# G803A.net
KiCad netlist of a schematic drawn in EAGLE
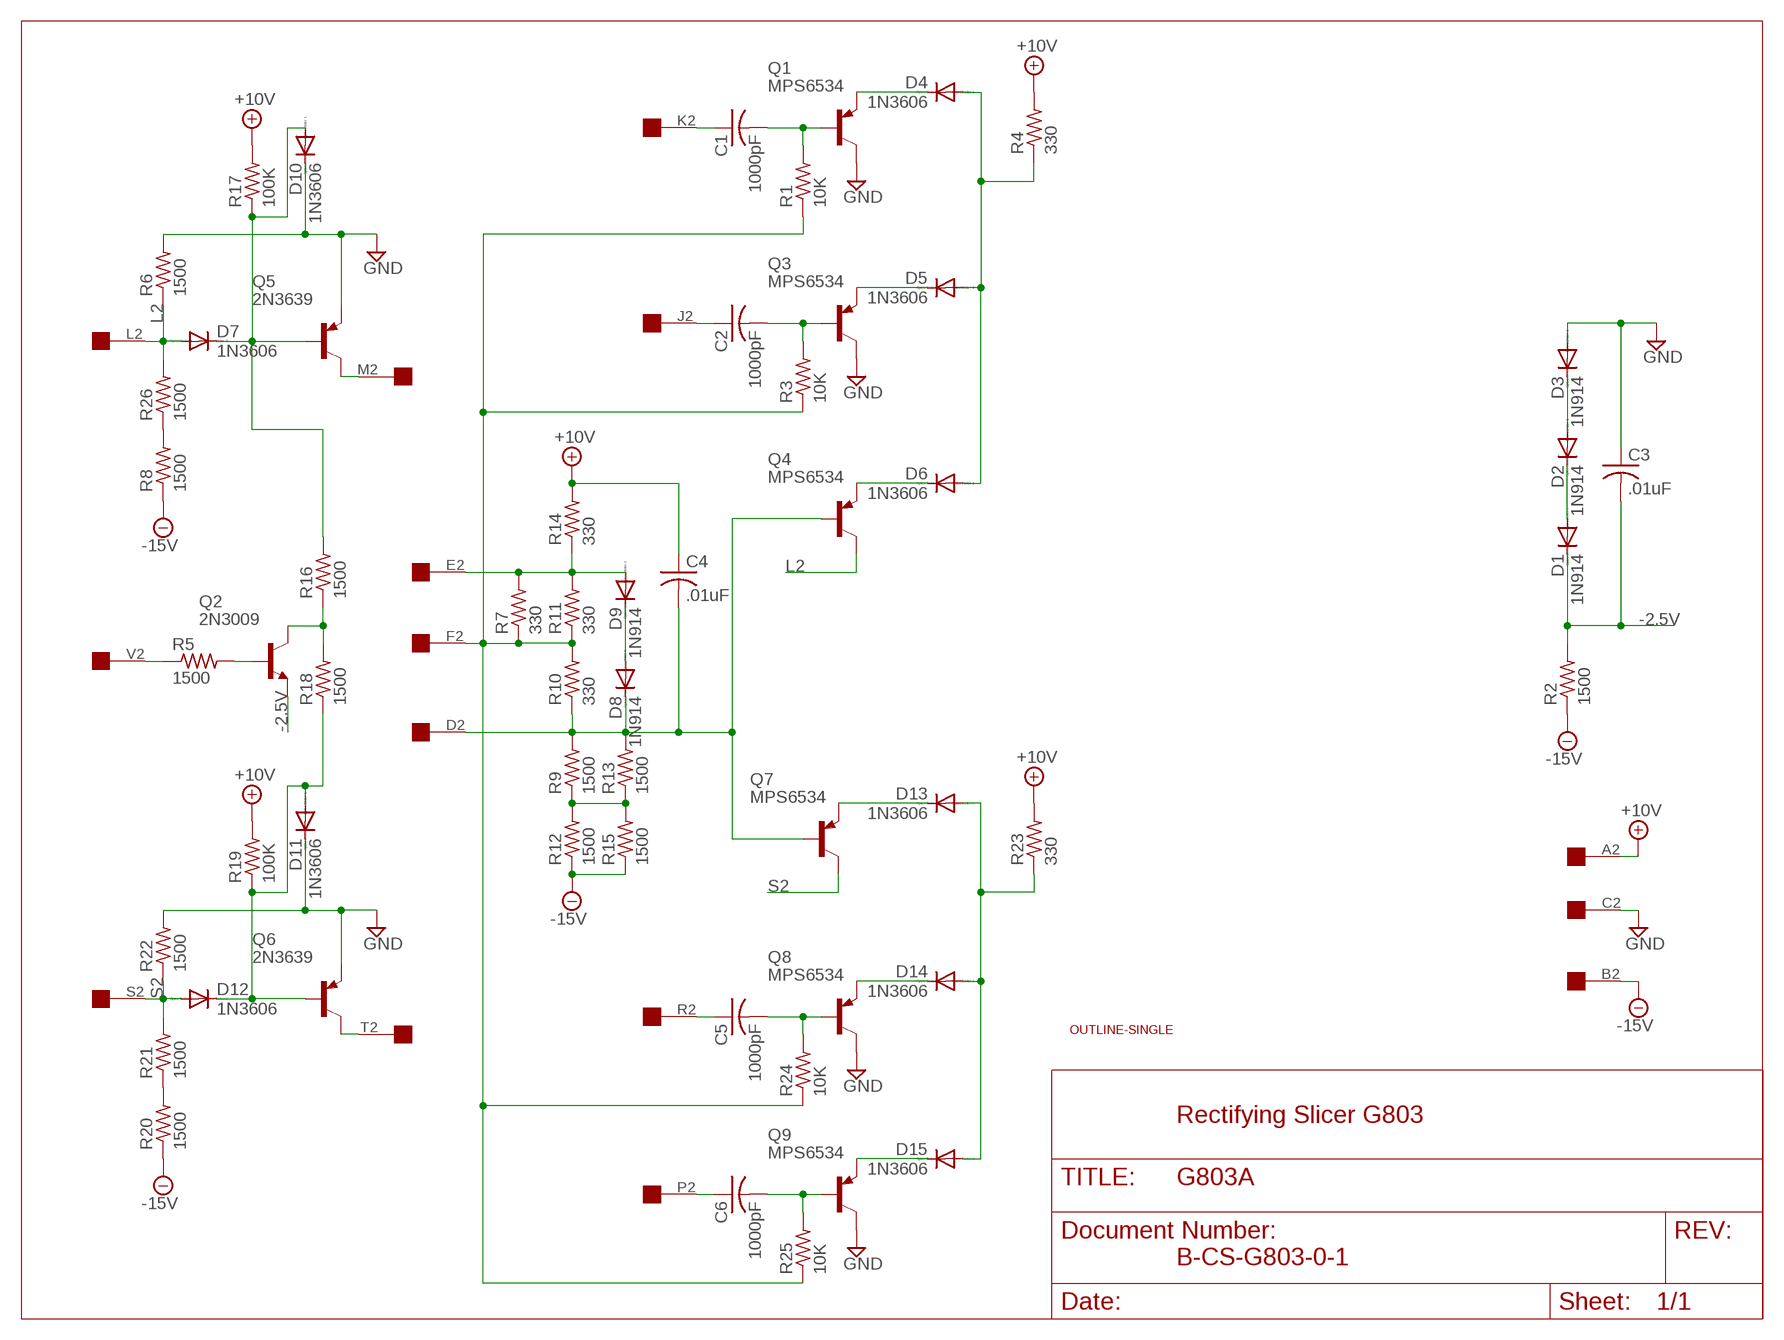
[diagram p0: schematic, sheet 1]

(export (version "E")
  (design (tool "Eeschema 10.0.6"))
  (components
    (comp (ref "C1")
      (value "1000pF")
      (footprint "eagle-import:C075-032X103")
      (libsource (lib "eagle-import") (part "C-US075-032X103"))
    )
    (comp (ref "C2")
      (value "1000pF")
      (footprint "eagle-import:C075-032X103")
      (libsource (lib "eagle-import") (part "C-US075-032X103"))
    )
    (comp (ref "C3")
      (value ".01uF")
      (footprint "eagle-import:C050-025X075")
      (libsource (lib "eagle-import") (part "C-US050-025X075"))
    )
    (comp (ref "C4")
      (value ".01uF")
      (footprint "eagle-import:C075-032X103")
      (libsource (lib "eagle-import") (part "C-US075-032X103"))
    )
    (comp (ref "C5")
      (value "1000pF")
      (footprint "eagle-import:C075-032X103")
      (libsource (lib "eagle-import") (part "C-US075-032X103"))
    )
    (comp (ref "C6")
      (value "1000pF")
      (footprint "eagle-import:C075-032X103")
      (libsource (lib "eagle-import") (part "C-US075-032X103"))
    )
    (comp (ref "D1")
      (value "1N914")
      (footprint "eagle-import:DO35-10")
      (libsource (lib "eagle-import") (part "1N4148DO35-10"))
    )
    (comp (ref "D2")
      (value "1N914")
      (footprint "eagle-import:DO35-10")
      (libsource (lib "eagle-import") (part "1N4148DO35-10"))
    )
    (comp (ref "D3")
      (value "1N914")
      (footprint "eagle-import:DO35-10")
      (libsource (lib "eagle-import") (part "1N4148DO35-10"))
    )
    (comp (ref "D4")
      (value "1N3606")
      (footprint "eagle-import:DO35-10")
      (libsource (lib "eagle-import") (part "1N4148DO35-10"))
    )
    (comp (ref "D5")
      (value "1N3606")
      (footprint "eagle-import:DO35-10")
      (libsource (lib "eagle-import") (part "1N4148DO35-10"))
    )
    (comp (ref "D6")
      (value "1N3606")
      (footprint "eagle-import:DO35-10")
      (libsource (lib "eagle-import") (part "1N4148DO35-10"))
    )
    (comp (ref "D7")
      (value "1N3606")
      (footprint "eagle-import:DO35-10")
      (libsource (lib "eagle-import") (part "1N4148DO35-10"))
    )
    (comp (ref "D8")
      (value "1N914")
      (footprint "eagle-import:DO35-10")
      (libsource (lib "eagle-import") (part "1N4148DO35-10"))
    )
    (comp (ref "D9")
      (value "1N914")
      (footprint "eagle-import:DO35-10")
      (libsource (lib "eagle-import") (part "1N4148DO35-10"))
    )
    (comp (ref "D10")
      (value "1N3606")
      (footprint "eagle-import:DO35-10")
      (libsource (lib "eagle-import") (part "1N4148DO35-10"))
    )
    (comp (ref "D11")
      (value "1N3606")
      (footprint "eagle-import:DO35-10")
      (libsource (lib "eagle-import") (part "1N4148DO35-10"))
    )
    (comp (ref "D12")
      (value "1N3606")
      (footprint "eagle-import:DO35-10")
      (libsource (lib "eagle-import") (part "1N4148DO35-10"))
    )
    (comp (ref "D13")
      (value "1N3606")
      (footprint "eagle-import:DO35-10")
      (libsource (lib "eagle-import") (part "1N4148DO35-10"))
    )
    (comp (ref "D14")
      (value "1N3606")
      (footprint "eagle-import:DO35-10")
      (libsource (lib "eagle-import") (part "1N4148DO35-10"))
    )
    (comp (ref "D15")
      (value "1N3606")
      (footprint "eagle-import:DO35-10")
      (libsource (lib "eagle-import") (part "1N4148DO35-10"))
    )
    (comp (ref "Q1")
      (value "MPS6534")
      (footprint "eagle-import:TO39")
      (libsource (lib "eagle-import") (part "2N2904"))
    )
    (comp (ref "Q2")
      (value "2N3009")
      (footprint "eagle-import:TO5")
      (libsource (lib "eagle-import") (part "2N2102"))
    )
    (comp (ref "Q3")
      (value "MPS6534")
      (footprint "eagle-import:TO39")
      (libsource (lib "eagle-import") (part "2N2904"))
    )
    (comp (ref "Q4")
      (value "MPS6534")
      (footprint "eagle-import:TO39")
      (libsource (lib "eagle-import") (part "2N2904"))
    )
    (comp (ref "Q5")
      (value "2N3639")
      (footprint "eagle-import:TO39")
      (libsource (lib "eagle-import") (part "2N2904"))
    )
    (comp (ref "Q6")
      (value "2N3639")
      (footprint "eagle-import:TO39")
      (libsource (lib "eagle-import") (part "2N2904"))
    )
    (comp (ref "Q7")
      (value "MPS6534")
      (footprint "eagle-import:TO39")
      (libsource (lib "eagle-import") (part "2N2904"))
    )
    (comp (ref "Q8")
      (value "MPS6534")
      (footprint "eagle-import:TO39")
      (libsource (lib "eagle-import") (part "2N2904"))
    )
    (comp (ref "Q9")
      (value "MPS6534")
      (footprint "eagle-import:TO39")
      (libsource (lib "eagle-import") (part "2N2904"))
    )
    (comp (ref "R1")
      (value "10K")
      (footprint "eagle-import:0207_10")
      (libsource (lib "eagle-import") (part "R-US_0207/10"))
    )
    (comp (ref "R2")
      (value "1500")
      (footprint "eagle-import:0207_10")
      (libsource (lib "eagle-import") (part "R-US_0207/10"))
    )
    (comp (ref "R3")
      (value "10K")
      (footprint "eagle-import:0207_10")
      (libsource (lib "eagle-import") (part "R-US_0207/10"))
    )
    (comp (ref "R4")
      (value "330")
      (footprint "eagle-import:0207_10")
      (libsource (lib "eagle-import") (part "R-US_0207/10"))
    )
    (comp (ref "R5")
      (value "1500")
      (footprint "eagle-import:0207_10")
      (libsource (lib "eagle-import") (part "R-US_0207/10"))
    )
    (comp (ref "R6")
      (value "1500")
      (footprint "eagle-import:0207_10")
      (libsource (lib "eagle-import") (part "R-US_0207/10"))
    )
    (comp (ref "R7")
      (value "330")
      (footprint "eagle-import:0207_10")
      (libsource (lib "eagle-import") (part "R-US_0207/10"))
    )
    (comp (ref "R8")
      (value "1500")
      (footprint "eagle-import:0207_10")
      (libsource (lib "eagle-import") (part "R-US_0207/10"))
    )
    (comp (ref "R9")
      (value "1500")
      (footprint "eagle-import:0207_10")
      (libsource (lib "eagle-import") (part "R-US_0207/10"))
    )
    (comp (ref "R10")
      (value "330")
      (footprint "eagle-import:0207_10")
      (libsource (lib "eagle-import") (part "R-US_0207/10"))
    )
    (comp (ref "R11")
      (value "330")
      (footprint "eagle-import:0207_10")
      (libsource (lib "eagle-import") (part "R-US_0207/10"))
    )
    (comp (ref "R12")
      (value "1500")
      (footprint "eagle-import:0207_10")
      (libsource (lib "eagle-import") (part "R-US_0207/10"))
    )
    (comp (ref "R13")
      (value "1500")
      (footprint "eagle-import:0207_10")
      (libsource (lib "eagle-import") (part "R-US_0207/10"))
    )
    (comp (ref "R14")
      (value "330")
      (footprint "eagle-import:0207_10")
      (libsource (lib "eagle-import") (part "R-US_0207/10"))
    )
    (comp (ref "R15")
      (value "1500")
      (footprint "eagle-import:0207_10")
      (libsource (lib "eagle-import") (part "R-US_0207/10"))
    )
    (comp (ref "R16")
      (value "1500")
      (footprint "eagle-import:0207_10")
      (libsource (lib "eagle-import") (part "R-US_0207/10"))
    )
    (comp (ref "R17")
      (value "100K")
      (footprint "eagle-import:0207_10")
      (libsource (lib "eagle-import") (part "R-US_0207/10"))
    )
    (comp (ref "R18")
      (value "1500")
      (footprint "eagle-import:0207_10")
      (libsource (lib "eagle-import") (part "R-US_0207/10"))
    )
    (comp (ref "R19")
      (value "100K")
      (footprint "eagle-import:0207_10")
      (libsource (lib "eagle-import") (part "R-US_0207/10"))
    )
    (comp (ref "R20")
      (value "1500")
      (footprint "eagle-import:0207_10")
      (libsource (lib "eagle-import") (part "R-US_0207/10"))
    )
    (comp (ref "R21")
      (value "1500")
      (footprint "eagle-import:0207_10")
      (libsource (lib "eagle-import") (part "R-US_0207/10"))
    )
    (comp (ref "R22")
      (value "1500")
      (footprint "eagle-import:0207_10")
      (libsource (lib "eagle-import") (part "R-US_0207/10"))
    )
    (comp (ref "R23")
      (value "330")
      (footprint "eagle-import:0207_10")
      (libsource (lib "eagle-import") (part "R-US_0207/10"))
    )
    (comp (ref "R24")
      (value "10K")
      (footprint "eagle-import:0207_10")
      (libsource (lib "eagle-import") (part "R-US_0207/10"))
    )
    (comp (ref "R25")
      (value "10K")
      (footprint "eagle-import:0207_10")
      (libsource (lib "eagle-import") (part "R-US_0207/10"))
    )
    (comp (ref "R26")
      (value "1500")
      (footprint "eagle-import:0207_10")
      (libsource (lib "eagle-import") (part "R-US_0207/10"))
    )
    (comp (ref "U$1")
      (value "OUTLINE-SINGLE")
      (footprint "eagle-import:SINGLE")
      (libsource (lib "eagle-import") (part "OUTLINE-SINGLE"))
    )
    (comp (ref "U$2")
      (value "EDGE-1")
      (footprint "eagle-import:EDGE-CON1")
      (libsource (lib "eagle-import") (part "EDGE-1"))
    )
  )
  (nets
    (net (code "1") (name "+10V") (class "Default")
      (node (ref "C4") (pin "1") (pinfunction "1_1") (pintype "passive"))
      (node (ref "R14") (pin "2") (pinfunction "2_2") (pintype "passive"))
      (node (ref "R17") (pin "2") (pinfunction "2_2") (pintype "passive"))
      (node (ref "R19") (pin "2") (pinfunction "2_2") (pintype "passive"))
      (node (ref "R23") (pin "2") (pinfunction "2_2") (pintype "passive"))
      (node (ref "R4") (pin "2") (pinfunction "2_2") (pintype "passive"))
      (node (ref "U$2") (pin "A2") (pinfunction "1_A2") (pintype "bidirectional"))
    )
    (net (code "2") (name "-15V") (class "Default")
      (node (ref "R12") (pin "1") (pinfunction "1_1") (pintype "passive"))
      (node (ref "R15") (pin "1") (pinfunction "1_1") (pintype "passive"))
      (node (ref "R2") (pin "1") (pinfunction "1_1") (pintype "passive"))
      (node (ref "R20") (pin "1") (pinfunction "1_1") (pintype "passive"))
      (node (ref "R8") (pin "1") (pinfunction "1_1") (pintype "passive"))
      (node (ref "U$2") (pin "B2") (pinfunction "1_B2") (pintype "bidirectional"))
    )
    (net (code "3") (name "/-2.5V") (class "Default")
      (node (ref "C3") (pin "2") (pinfunction "2_2") (pintype "passive"))
      (node (ref "D1") (pin "C") (pinfunction "C_C") (pintype "passive"))
      (node (ref "Q2") (pin "1") (pinfunction "E_1") (pintype "passive"))
      (node (ref "R2") (pin "2") (pinfunction "2_2") (pintype "passive"))
    )
    (net (code "4") (name "/L2") (class "Default")
      (node (ref "D7") (pin "A") (pinfunction "A_A") (pintype "passive"))
      (node (ref "Q4") (pin "3") (pinfunction "C_3") (pintype "passive"))
      (node (ref "R26") (pin "2") (pinfunction "2_2") (pintype "passive"))
      (node (ref "R6") (pin "1") (pinfunction "1_1") (pintype "passive"))
      (node (ref "U$2") (pin "L2") (pinfunction "1_L2") (pintype "bidirectional"))
    )
    (net (code "5") (name "/S2") (class "Default")
      (node (ref "D12") (pin "A") (pinfunction "A_A") (pintype "passive"))
      (node (ref "Q7") (pin "3") (pinfunction "C_3") (pintype "passive"))
      (node (ref "R21") (pin "2") (pinfunction "2_2") (pintype "passive"))
      (node (ref "R22") (pin "1") (pinfunction "1_1") (pintype "passive"))
      (node (ref "U$2") (pin "S2") (pinfunction "1_S2") (pintype "bidirectional"))
    )
    (net (code "6") (name "GND") (class "Default")
      (node (ref "C3") (pin "1") (pinfunction "1_1") (pintype "passive"))
      (node (ref "D10") (pin "C") (pinfunction "C_C") (pintype "passive"))
      (node (ref "D11") (pin "C") (pinfunction "C_C") (pintype "passive"))
      (node (ref "D3") (pin "A") (pinfunction "A_A") (pintype "passive"))
      (node (ref "Q1") (pin "3") (pinfunction "C_3") (pintype "passive"))
      (node (ref "Q3") (pin "3") (pinfunction "C_3") (pintype "passive"))
      (node (ref "Q5") (pin "1") (pinfunction "E_1") (pintype "passive"))
      (node (ref "Q6") (pin "1") (pinfunction "E_1") (pintype "passive"))
      (node (ref "Q8") (pin "3") (pinfunction "C_3") (pintype "passive"))
      (node (ref "Q9") (pin "3") (pinfunction "C_3") (pintype "passive"))
      (node (ref "R22") (pin "2") (pinfunction "2_2") (pintype "passive"))
      (node (ref "R6") (pin "2") (pinfunction "2_2") (pintype "passive"))
      (node (ref "U$2") (pin "C2") (pinfunction "1_C2") (pintype "bidirectional"))
    )
    (net (code "7") (name "Net-(D1-PadA)") (class "Default")
      (node (ref "D1") (pin "A") (pinfunction "A_A") (pintype "passive"))
      (node (ref "D2") (pin "C") (pinfunction "C_C") (pintype "passive"))
    )
    (net (code "8") (name "Net-(D2-PadA)") (class "Default")
      (node (ref "D2") (pin "A") (pinfunction "A_A") (pintype "passive"))
      (node (ref "D3") (pin "C") (pinfunction "C_C") (pintype "passive"))
    )
    (net (code "9") (name "Net-(D4-PadA)") (class "Default")
      (node (ref "D4") (pin "A") (pinfunction "A_A") (pintype "passive"))
      (node (ref "D5") (pin "A") (pinfunction "A_A") (pintype "passive"))
      (node (ref "D6") (pin "A") (pinfunction "A_A") (pintype "passive"))
      (node (ref "R4") (pin "1") (pinfunction "1_1") (pintype "passive"))
    )
    (net (code "10") (name "Net-(D8-PadA)") (class "Default")
      (node (ref "D8") (pin "A") (pinfunction "A_A") (pintype "passive"))
      (node (ref "D9") (pin "C") (pinfunction "C_C") (pintype "passive"))
    )
    (net (code "11") (name "Net-(D13-PadA)") (class "Default")
      (node (ref "D13") (pin "A") (pinfunction "A_A") (pintype "passive"))
      (node (ref "D14") (pin "A") (pinfunction "A_A") (pintype "passive"))
      (node (ref "D15") (pin "A") (pinfunction "A_A") (pintype "passive"))
      (node (ref "R23") (pin "1") (pinfunction "1_1") (pintype "passive"))
    )
    (net (code "12") (name "Net-(Q1-B)") (class "Default")
      (node (ref "C1") (pin "2") (pinfunction "2_2") (pintype "passive"))
      (node (ref "Q1") (pin "2") (pinfunction "B_2") (pintype "passive"))
      (node (ref "R1") (pin "2") (pinfunction "2_2") (pintype "passive"))
    )
    (net (code "13") (name "Net-(Q1-E)") (class "Default")
      (node (ref "D4") (pin "C") (pinfunction "C_C") (pintype "passive"))
      (node (ref "Q1") (pin "1") (pinfunction "E_1") (pintype "passive"))
    )
    (net (code "14") (name "Net-(Q2-B)") (class "Default")
      (node (ref "Q2") (pin "2") (pinfunction "B_2") (pintype "passive"))
      (node (ref "R5") (pin "2") (pinfunction "2_2") (pintype "passive"))
    )
    (net (code "15") (name "Net-(Q2-C)") (class "Default")
      (node (ref "Q2") (pin "3") (pinfunction "C_3") (pintype "passive"))
      (node (ref "R16") (pin "1") (pinfunction "1_1") (pintype "passive"))
      (node (ref "R18") (pin "2") (pinfunction "2_2") (pintype "passive"))
    )
    (net (code "16") (name "Net-(Q3-B)") (class "Default")
      (node (ref "C2") (pin "2") (pinfunction "2_2") (pintype "passive"))
      (node (ref "Q3") (pin "2") (pinfunction "B_2") (pintype "passive"))
      (node (ref "R3") (pin "2") (pinfunction "2_2") (pintype "passive"))
    )
    (net (code "17") (name "Net-(Q3-E)") (class "Default")
      (node (ref "D5") (pin "C") (pinfunction "C_C") (pintype "passive"))
      (node (ref "Q3") (pin "1") (pinfunction "E_1") (pintype "passive"))
    )
    (net (code "18") (name "Net-(Q4-B)") (class "Default")
      (node (ref "C4") (pin "2") (pinfunction "2_2") (pintype "passive"))
      (node (ref "D8") (pin "C") (pinfunction "C_C") (pintype "passive"))
      (node (ref "Q4") (pin "2") (pinfunction "B_2") (pintype "passive"))
      (node (ref "Q7") (pin "2") (pinfunction "B_2") (pintype "passive"))
      (node (ref "R10") (pin "1") (pinfunction "1_1") (pintype "passive"))
      (node (ref "R13") (pin "2") (pinfunction "2_2") (pintype "passive"))
      (node (ref "R9") (pin "2") (pinfunction "2_2") (pintype "passive"))
      (node (ref "U$2") (pin "D2") (pinfunction "1_D2") (pintype "bidirectional"))
    )
    (net (code "19") (name "Net-(Q4-E)") (class "Default")
      (node (ref "D6") (pin "C") (pinfunction "C_C") (pintype "passive"))
      (node (ref "Q4") (pin "1") (pinfunction "E_1") (pintype "passive"))
    )
    (net (code "20") (name "Net-(Q5-B)") (class "Default")
      (node (ref "D10") (pin "A") (pinfunction "A_A") (pintype "passive"))
      (node (ref "D7") (pin "C") (pinfunction "C_C") (pintype "passive"))
      (node (ref "Q5") (pin "2") (pinfunction "B_2") (pintype "passive"))
      (node (ref "R16") (pin "2") (pinfunction "2_2") (pintype "passive"))
      (node (ref "R17") (pin "1") (pinfunction "1_1") (pintype "passive"))
    )
    (net (code "21") (name "Net-(Q5-C)") (class "Default")
      (node (ref "Q5") (pin "3") (pinfunction "C_3") (pintype "passive"))
      (node (ref "U$2") (pin "M2") (pinfunction "1_M2") (pintype "bidirectional"))
    )
    (net (code "22") (name "Net-(Q6-B)") (class "Default")
      (node (ref "D11") (pin "A") (pinfunction "A_A") (pintype "passive"))
      (node (ref "D12") (pin "C") (pinfunction "C_C") (pintype "passive"))
      (node (ref "Q6") (pin "2") (pinfunction "B_2") (pintype "passive"))
      (node (ref "R18") (pin "1") (pinfunction "1_1") (pintype "passive"))
      (node (ref "R19") (pin "1") (pinfunction "1_1") (pintype "passive"))
    )
    (net (code "23") (name "Net-(Q6-C)") (class "Default")
      (node (ref "Q6") (pin "3") (pinfunction "C_3") (pintype "passive"))
      (node (ref "U$2") (pin "T2") (pinfunction "1_T2") (pintype "bidirectional"))
    )
    (net (code "24") (name "Net-(Q7-E)") (class "Default")
      (node (ref "D13") (pin "C") (pinfunction "C_C") (pintype "passive"))
      (node (ref "Q7") (pin "1") (pinfunction "E_1") (pintype "passive"))
    )
    (net (code "25") (name "Net-(Q8-B)") (class "Default")
      (node (ref "C5") (pin "2") (pinfunction "2_2") (pintype "passive"))
      (node (ref "Q8") (pin "2") (pinfunction "B_2") (pintype "passive"))
      (node (ref "R24") (pin "2") (pinfunction "2_2") (pintype "passive"))
    )
    (net (code "26") (name "Net-(Q8-E)") (class "Default")
      (node (ref "D14") (pin "C") (pinfunction "C_C") (pintype "passive"))
      (node (ref "Q8") (pin "1") (pinfunction "E_1") (pintype "passive"))
    )
    (net (code "27") (name "Net-(Q9-B)") (class "Default")
      (node (ref "C6") (pin "2") (pinfunction "2_2") (pintype "passive"))
      (node (ref "Q9") (pin "2") (pinfunction "B_2") (pintype "passive"))
      (node (ref "R25") (pin "2") (pinfunction "2_2") (pintype "passive"))
    )
    (net (code "28") (name "Net-(Q9-E)") (class "Default")
      (node (ref "D15") (pin "C") (pinfunction "C_C") (pintype "passive"))
      (node (ref "Q9") (pin "1") (pinfunction "E_1") (pintype "passive"))
    )
    (net (code "29") (name "Net-(R12-Pad2)") (class "Default")
      (node (ref "R12") (pin "2") (pinfunction "2_2") (pintype "passive"))
      (node (ref "R13") (pin "1") (pinfunction "1_1") (pintype "passive"))
      (node (ref "R15") (pin "2") (pinfunction "2_2") (pintype "passive"))
      (node (ref "R9") (pin "1") (pinfunction "1_1") (pintype "passive"))
    )
    (net (code "30") (name "Net-(R20-Pad2)") (class "Default")
      (node (ref "R20") (pin "2") (pinfunction "2_2") (pintype "passive"))
      (node (ref "R21") (pin "1") (pinfunction "1_1") (pintype "passive"))
    )
    (net (code "31") (name "Net-(R26-Pad1)") (class "Default")
      (node (ref "R26") (pin "1") (pinfunction "1_1") (pintype "passive"))
      (node (ref "R8") (pin "2") (pinfunction "2_2") (pintype "passive"))
    )
    (net (code "32") (name "Net-(U$2E-1)") (class "Default")
      (node (ref "D9") (pin "A") (pinfunction "A_A") (pintype "passive"))
      (node (ref "R11") (pin "2") (pinfunction "2_2") (pintype "passive"))
      (node (ref "R14") (pin "1") (pinfunction "1_1") (pintype "passive"))
      (node (ref "R7") (pin "2") (pinfunction "2_2") (pintype "passive"))
      (node (ref "U$2") (pin "E2") (pinfunction "1_E2") (pintype "bidirectional"))
    )
    (net (code "33") (name "Net-(U$2F-1)") (class "Default")
      (node (ref "R1") (pin "1") (pinfunction "1_1") (pintype "passive"))
      (node (ref "R10") (pin "2") (pinfunction "2_2") (pintype "passive"))
      (node (ref "R11") (pin "1") (pinfunction "1_1") (pintype "passive"))
      (node (ref "R24") (pin "1") (pinfunction "1_1") (pintype "passive"))
      (node (ref "R25") (pin "1") (pinfunction "1_1") (pintype "passive"))
      (node (ref "R3") (pin "1") (pinfunction "1_1") (pintype "passive"))
      (node (ref "R7") (pin "1") (pinfunction "1_1") (pintype "passive"))
      (node (ref "U$2") (pin "F2") (pinfunction "1_F2") (pintype "bidirectional"))
    )
    (net (code "34") (name "Net-(U$2H-1)") (class "Default")
      (node (ref "C2") (pin "1") (pinfunction "1_1") (pintype "passive"))
      (node (ref "U$2") (pin "J2") (pinfunction "1_J2") (pintype "bidirectional"))
    )
    (net (code "35") (name "Net-(U$2I-1)") (class "Default")
      (node (ref "C1") (pin "1") (pinfunction "1_1") (pintype "passive"))
      (node (ref "U$2") (pin "K2") (pinfunction "1_K2") (pintype "bidirectional"))
    )
    (net (code "36") (name "Net-(U$2M-1)") (class "Default")
      (node (ref "C6") (pin "1") (pinfunction "1_1") (pintype "passive"))
      (node (ref "U$2") (pin "P2") (pinfunction "1_P2") (pintype "bidirectional"))
    )
    (net (code "37") (name "Net-(U$2N-1)") (class "Default")
      (node (ref "C5") (pin "1") (pinfunction "1_1") (pintype "passive"))
      (node (ref "U$2") (pin "R2") (pinfunction "1_R2") (pintype "bidirectional"))
    )
    (net (code "38") (name "Net-(U$2R-1)") (class "Default")
      (node (ref "R5") (pin "1") (pinfunction "1_1") (pintype "passive"))
      (node (ref "U$2") (pin "V2") (pinfunction "1_V2") (pintype "bidirectional"))
    )
  )
)
